# amp_kt3102_summator_v_1_0.net
KiCad netlist of a schematic drawn in EAGLE
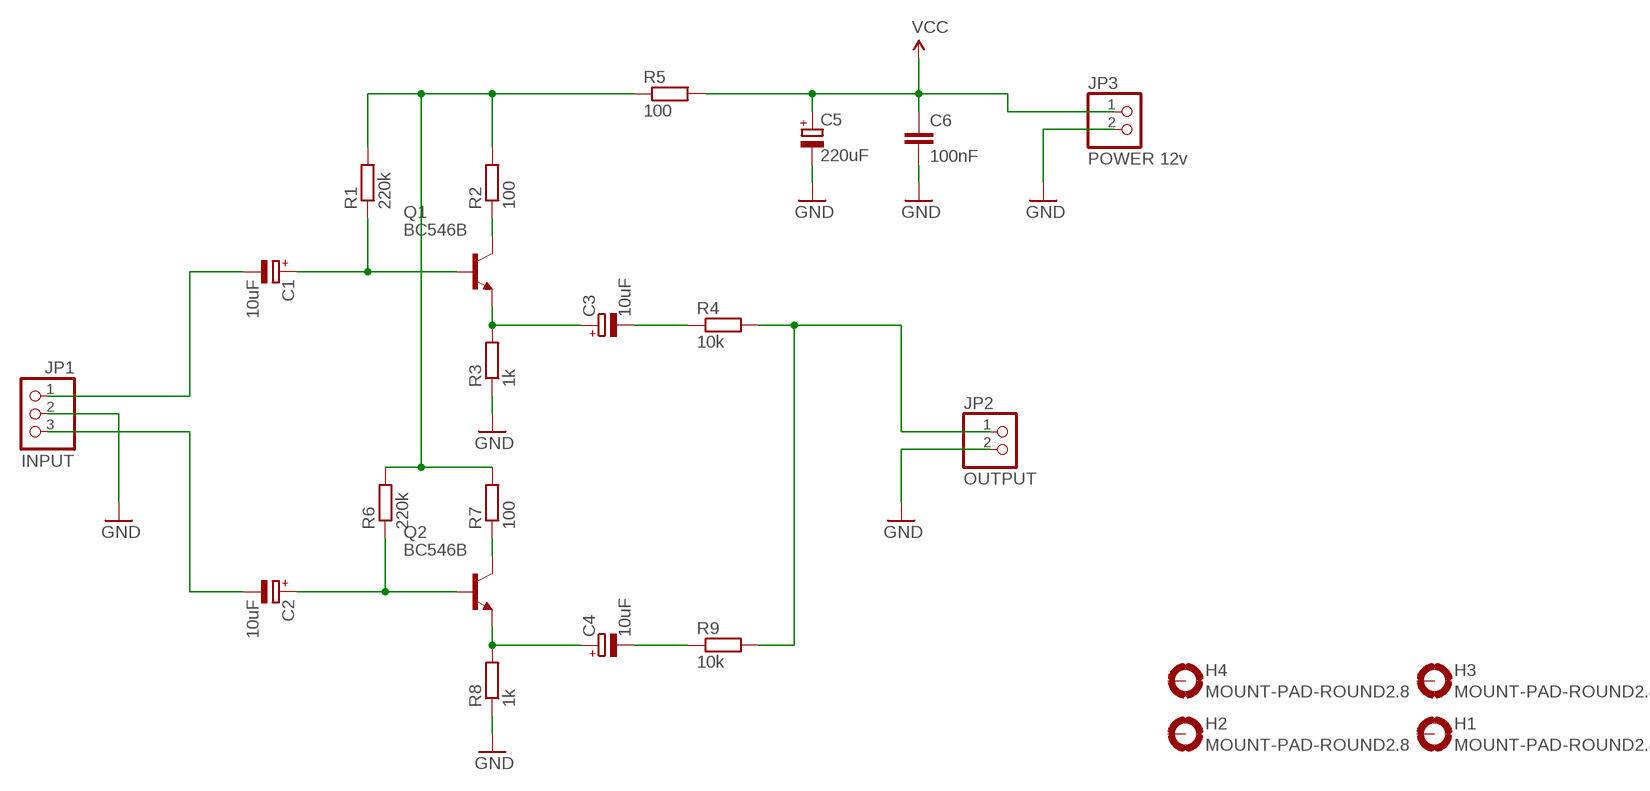
[diagram p0: schematic, sheet 1]

(export (version "E")
  (design (tool "Eeschema 10.0.6"))
  (components
    (comp (ref "C1")
      (value "10uF")
      (footprint "eagle-import:E2,5-5")
      (libsource (lib "eagle-import") (part "CPOL-EUE2.5-5"))
    )
    (comp (ref "C2")
      (value "10uF")
      (footprint "eagle-import:E2,5-5")
      (libsource (lib "eagle-import") (part "CPOL-EUE2.5-5"))
    )
    (comp (ref "C3")
      (value "10uF")
      (footprint "eagle-import:E2,5-5")
      (libsource (lib "eagle-import") (part "CPOL-EUE2.5-5"))
    )
    (comp (ref "C4")
      (value "10uF")
      (footprint "eagle-import:E2,5-5")
      (libsource (lib "eagle-import") (part "CPOL-EUE2.5-5"))
    )
    (comp (ref "C5")
      (value "220uF")
      (footprint "eagle-import:E3,5-8")
      (libsource (lib "eagle-import") (part "CPOL-EUE3.5-8"))
    )
    (comp (ref "C6")
      (value "100nF")
      (footprint "eagle-import:C050-025X075")
      (libsource (lib "eagle-import") (part "C-EU050-025X075"))
    )
    (comp (ref "H1")
      (value "MOUNT-PAD-ROUND2.8")
      (footprint "eagle-import:2,8-PAD")
      (libsource (lib "eagle-import") (part "MOUNT-PAD-ROUND2.8"))
    )
    (comp (ref "H2")
      (value "MOUNT-PAD-ROUND2.8")
      (footprint "eagle-import:2,8-PAD")
      (libsource (lib "eagle-import") (part "MOUNT-PAD-ROUND2.8"))
    )
    (comp (ref "H3")
      (value "MOUNT-PAD-ROUND2.8")
      (footprint "eagle-import:2,8-PAD")
      (libsource (lib "eagle-import") (part "MOUNT-PAD-ROUND2.8"))
    )
    (comp (ref "H4")
      (value "MOUNT-PAD-ROUND2.8")
      (footprint "eagle-import:2,8-PAD")
      (libsource (lib "eagle-import") (part "MOUNT-PAD-ROUND2.8"))
    )
    (comp (ref "JP1")
      (value "INPUT")
      (footprint "eagle-import:1X03")
      (libsource (lib "eagle-import") (part "PINHD-1X3"))
    )
    (comp (ref "JP2")
      (value "OUTPUT")
      (footprint "eagle-import:1X02")
      (libsource (lib "eagle-import") (part "PINHD-1X2"))
    )
    (comp (ref "JP3")
      (value "POWER 12v")
      (footprint "eagle-import:1X02")
      (libsource (lib "eagle-import") (part "PINHD-1X2"))
    )
    (comp (ref "Q1")
      (value "BC546B")
      (footprint "eagle-import:TO92-EBC")
      (libsource (lib "eagle-import") (part "BC546B"))
    )
    (comp (ref "Q2")
      (value "BC546B")
      (footprint "eagle-import:TO92-EBC")
      (libsource (lib "eagle-import") (part "BC546B"))
    )
    (comp (ref "R1")
      (value "220k")
      (footprint "eagle-import:0204_7")
      (libsource (lib "eagle-import") (part "R-EU_0204/7"))
    )
    (comp (ref "R2")
      (value "100")
      (footprint "eagle-import:0204_7")
      (libsource (lib "eagle-import") (part "R-EU_0204/7"))
    )
    (comp (ref "R3")
      (value "1k")
      (footprint "eagle-import:0204_7")
      (libsource (lib "eagle-import") (part "R-EU_0204/7"))
    )
    (comp (ref "R4")
      (value "10k")
      (footprint "eagle-import:0204_7")
      (libsource (lib "eagle-import") (part "R-EU_0204/7"))
    )
    (comp (ref "R5")
      (value "100")
      (footprint "eagle-import:0204_7")
      (libsource (lib "eagle-import") (part "R-EU_0204/7"))
    )
    (comp (ref "R6")
      (value "220k")
      (footprint "eagle-import:0204_7")
      (libsource (lib "eagle-import") (part "R-EU_0204/7"))
    )
    (comp (ref "R7")
      (value "100")
      (footprint "eagle-import:0204_7")
      (libsource (lib "eagle-import") (part "R-EU_0204/7"))
    )
    (comp (ref "R8")
      (value "1k")
      (footprint "eagle-import:0204_7")
      (libsource (lib "eagle-import") (part "R-EU_0204/7"))
    )
    (comp (ref "R9")
      (value "10k")
      (footprint "eagle-import:0204_7")
      (libsource (lib "eagle-import") (part "R-EU_0204/7"))
    )
  )
  (nets
    (net (code "1") (name "GND") (class "Default")
      (node (ref "C5") (pin "-") (pinfunction "-_-") (pintype "passive"))
      (node (ref "C6") (pin "2") (pinfunction "2_2") (pintype "passive"))
      (node (ref "JP1") (pin "2") (pinfunction "2_2") (pintype "passive"))
      (node (ref "JP2") (pin "2") (pinfunction "2_2") (pintype "passive"))
      (node (ref "JP3") (pin "2") (pinfunction "2_2") (pintype "passive"))
      (node (ref "R3") (pin "1") (pinfunction "1_1") (pintype "passive"))
      (node (ref "R8") (pin "1") (pinfunction "1_1") (pintype "passive"))
    )
    (net (code "2") (name "Net-(C1-Pad+)") (class "Default")
      (node (ref "C1") (pin "+") (pinfunction "+_+") (pintype "passive"))
      (node (ref "Q1") (pin "B") (pinfunction "B_B") (pintype "passive"))
      (node (ref "R1") (pin "1") (pinfunction "1_1") (pintype "passive"))
    )
    (net (code "3") (name "Net-(C1-Pad-)") (class "Default")
      (node (ref "C1") (pin "-") (pinfunction "-_-") (pintype "passive"))
      (node (ref "JP1") (pin "1") (pinfunction "1_1") (pintype "passive"))
    )
    (net (code "4") (name "Net-(C2-Pad+)") (class "Default")
      (node (ref "C2") (pin "+") (pinfunction "+_+") (pintype "passive"))
      (node (ref "Q2") (pin "B") (pinfunction "B_B") (pintype "passive"))
      (node (ref "R6") (pin "1") (pinfunction "1_1") (pintype "passive"))
    )
    (net (code "5") (name "Net-(C2-Pad-)") (class "Default")
      (node (ref "C2") (pin "-") (pinfunction "-_-") (pintype "passive"))
      (node (ref "JP1") (pin "3") (pinfunction "3_3") (pintype "passive"))
    )
    (net (code "6") (name "Net-(C3-Pad+)") (class "Default")
      (node (ref "C3") (pin "+") (pinfunction "+_+") (pintype "passive"))
      (node (ref "Q1") (pin "E") (pinfunction "E_E") (pintype "passive"))
      (node (ref "R3") (pin "2") (pinfunction "2_2") (pintype "passive"))
    )
    (net (code "7") (name "Net-(C3-Pad-)") (class "Default")
      (node (ref "C3") (pin "-") (pinfunction "-_-") (pintype "passive"))
      (node (ref "R4") (pin "1") (pinfunction "1_1") (pintype "passive"))
    )
    (net (code "8") (name "Net-(C4-Pad+)") (class "Default")
      (node (ref "C4") (pin "+") (pinfunction "+_+") (pintype "passive"))
      (node (ref "Q2") (pin "E") (pinfunction "E_E") (pintype "passive"))
      (node (ref "R8") (pin "2") (pinfunction "2_2") (pintype "passive"))
    )
    (net (code "9") (name "Net-(C4-Pad-)") (class "Default")
      (node (ref "C4") (pin "-") (pinfunction "-_-") (pintype "passive"))
      (node (ref "R9") (pin "1") (pinfunction "1_1") (pintype "passive"))
    )
    (net (code "10") (name "Net-(JP2-Pad1)") (class "Default")
      (node (ref "JP2") (pin "1") (pinfunction "1_1") (pintype "passive"))
      (node (ref "R4") (pin "2") (pinfunction "2_2") (pintype "passive"))
      (node (ref "R9") (pin "2") (pinfunction "2_2") (pintype "passive"))
    )
    (net (code "11") (name "Net-(Q1-PadC)") (class "Default")
      (node (ref "Q1") (pin "C") (pinfunction "C_C") (pintype "passive"))
      (node (ref "R2") (pin "1") (pinfunction "1_1") (pintype "passive"))
    )
    (net (code "12") (name "Net-(Q2-PadC)") (class "Default")
      (node (ref "Q2") (pin "C") (pinfunction "C_C") (pintype "passive"))
      (node (ref "R7") (pin "1") (pinfunction "1_1") (pintype "passive"))
    )
    (net (code "13") (name "Net-(R1-Pad2)") (class "Default")
      (node (ref "R1") (pin "2") (pinfunction "2_2") (pintype "passive"))
      (node (ref "R2") (pin "2") (pinfunction "2_2") (pintype "passive"))
      (node (ref "R5") (pin "1") (pinfunction "1_1") (pintype "passive"))
      (node (ref "R6") (pin "2") (pinfunction "2_2") (pintype "passive"))
      (node (ref "R7") (pin "2") (pinfunction "2_2") (pintype "passive"))
    )
    (net (code "14") (name "VCC") (class "Default")
      (node (ref "C5") (pin "+") (pinfunction "+_+") (pintype "passive"))
      (node (ref "C6") (pin "1") (pinfunction "1_1") (pintype "passive"))
      (node (ref "JP3") (pin "1") (pinfunction "1_1") (pintype "passive"))
      (node (ref "R5") (pin "2") (pinfunction "2_2") (pintype "passive"))
    )
    (net (code "15") (name "unconnected-(H1-MOUNT-PadB2,8)") (class "Default")
      (node (ref "H1") (pin "B2,8") (pinfunction "MOUNT_B2,8") (pintype "passive"))
    )
    (net (code "16") (name "unconnected-(H2-MOUNT-PadB2,8)") (class "Default")
      (node (ref "H2") (pin "B2,8") (pinfunction "MOUNT_B2,8") (pintype "passive"))
    )
    (net (code "17") (name "unconnected-(H3-MOUNT-PadB2,8)") (class "Default")
      (node (ref "H3") (pin "B2,8") (pinfunction "MOUNT_B2,8") (pintype "passive"))
    )
    (net (code "18") (name "unconnected-(H4-MOUNT-PadB2,8)") (class "Default")
      (node (ref "H4") (pin "B2,8") (pinfunction "MOUNT_B2,8") (pintype "passive"))
    )
  )
)
